# ESIOT.net
KiCad netlist of a schematic drawn in EasyEDA Pro
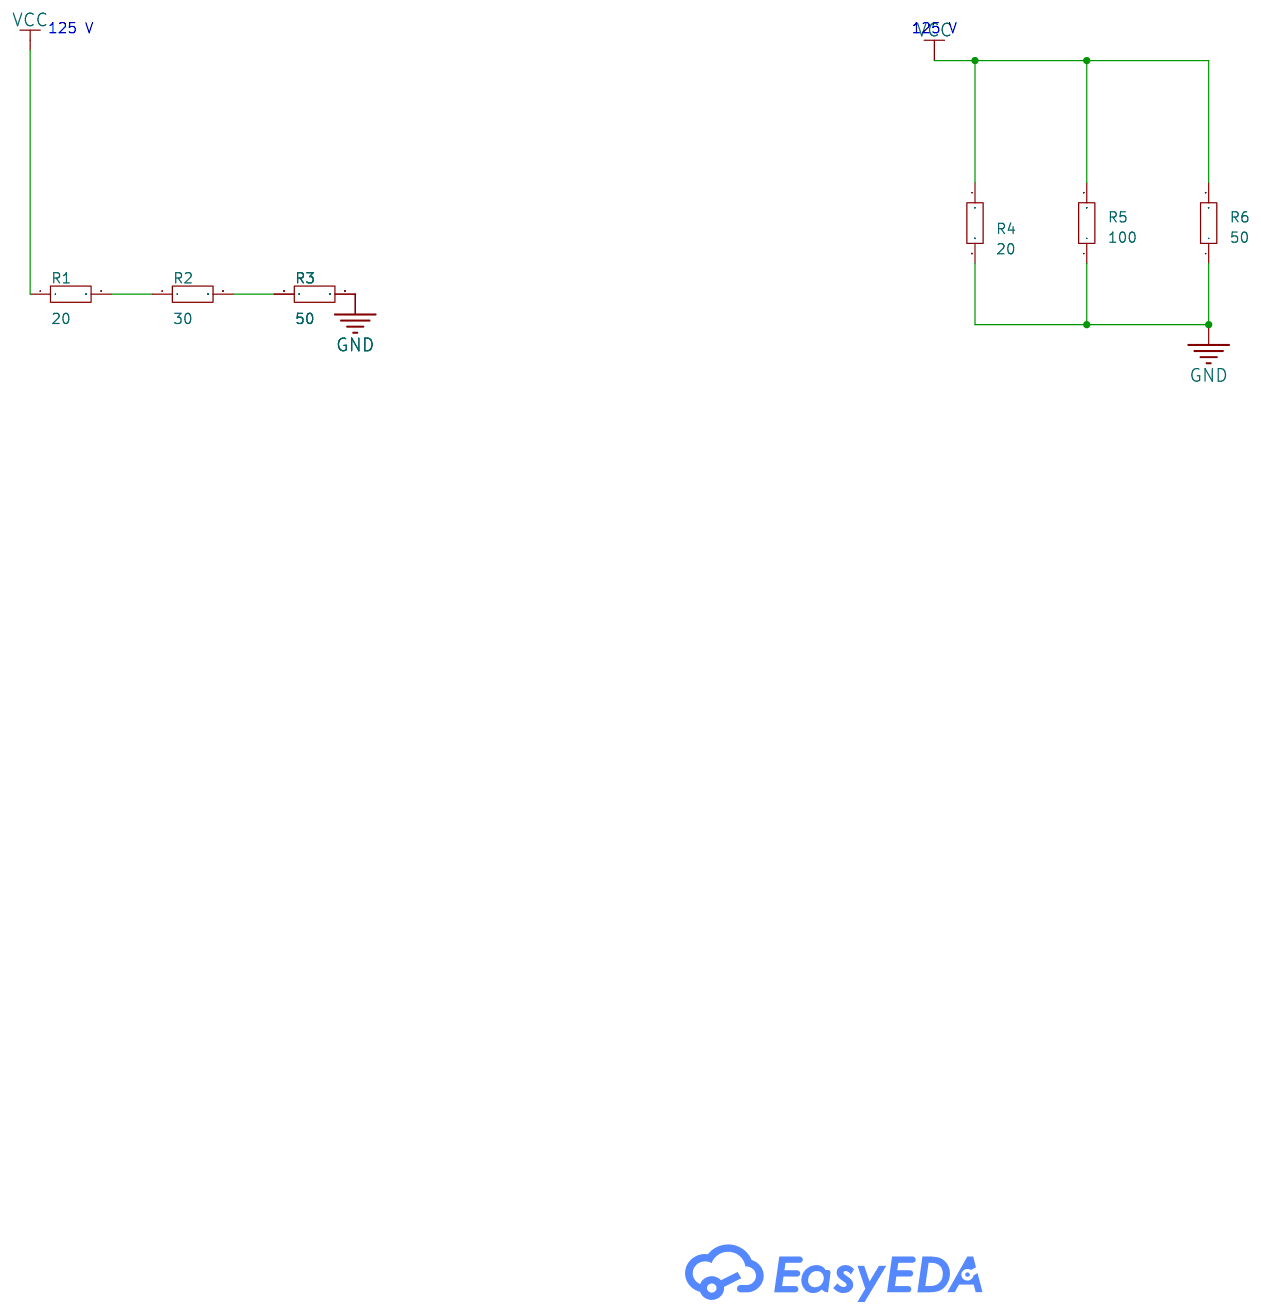
[diagram p0: P1]
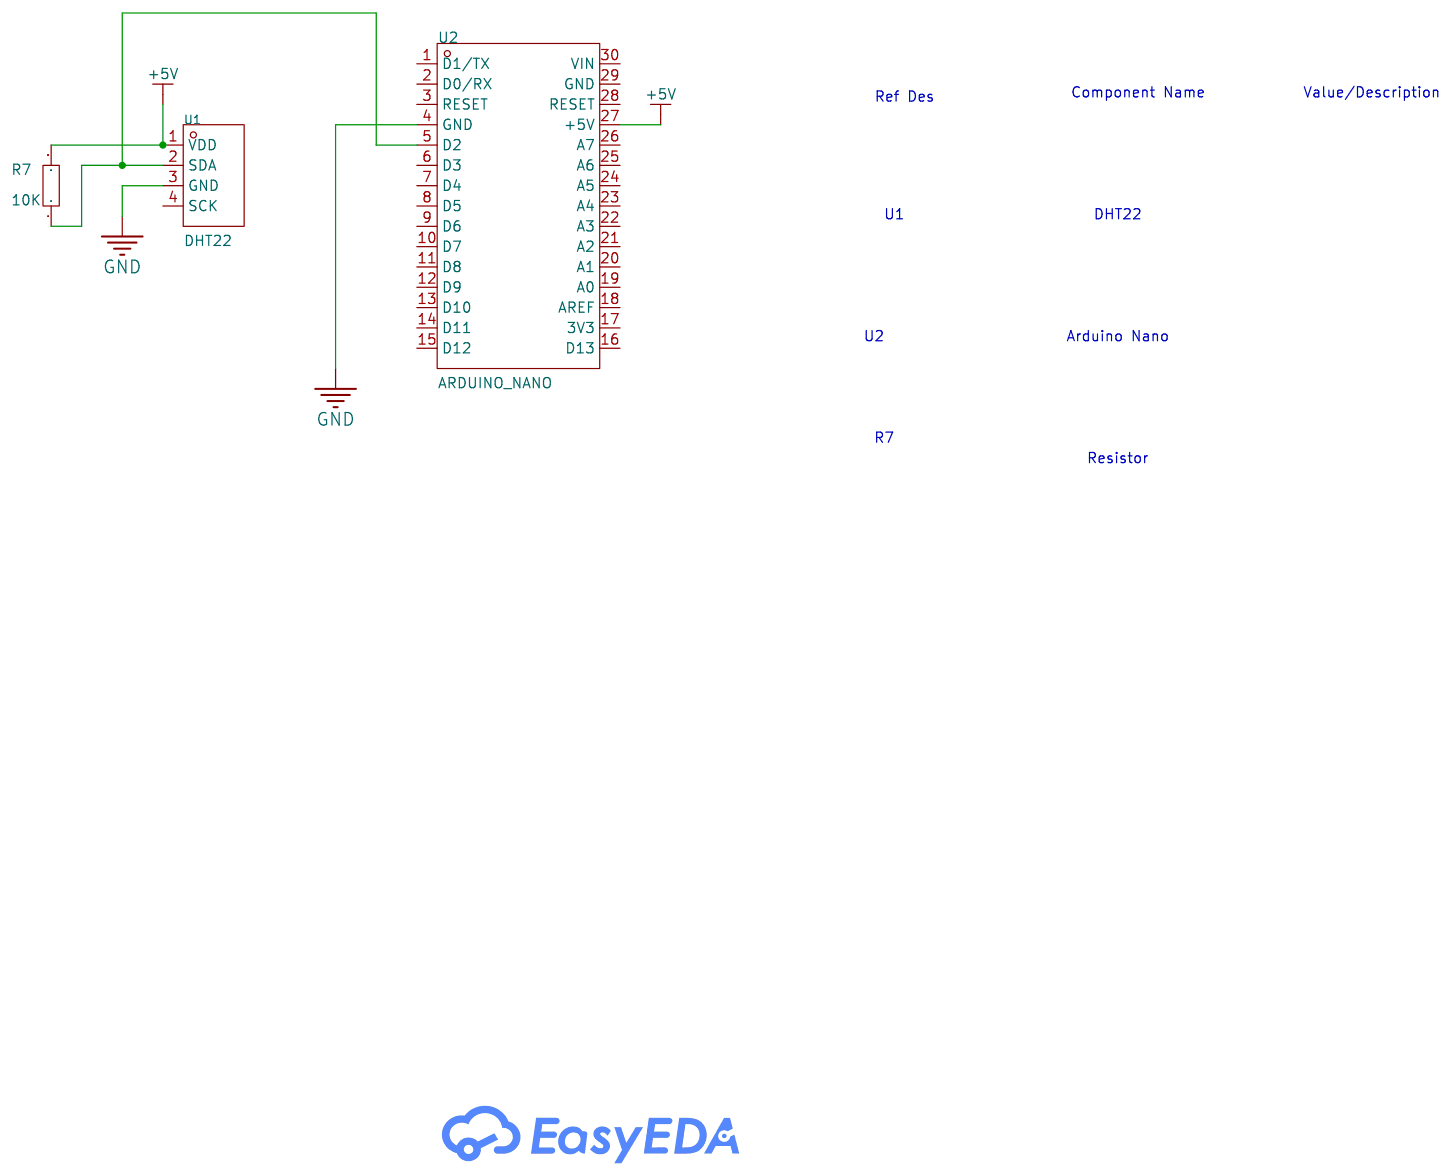
[diagram p1: P2]

(export (version "E")
  (design (tool "Eeschema 10.0.6"))
  (components
    (comp (ref "R1") (value "20") (footprint "easyedapro:R0603") (libsource (lib "easyedapro") (part "Res")))
    (comp (ref "R2") (value "30") (footprint "easyedapro:R0603") (libsource (lib "easyedapro") (part "Res")))
    (comp (ref "R3") (value "50") (footprint "easyedapro:R0603") (libsource (lib "easyedapro") (part "Res")))
    (comp (ref "R4") (value "20") (footprint "easyedapro:R0603") (libsource (lib "easyedapro") (part "Res")))
    (comp (ref "R5") (value "100") (footprint "easyedapro:R0603") (libsource (lib "easyedapro") (part "Res")))
    (comp (ref "R6") (value "50") (footprint "easyedapro:R0603") (libsource (lib "easyedapro") (part "Res")))
    (comp (ref "R7") (value "10K") (footprint "easyedapro:R0603") (libsource (lib "easyedapro") (part "Res")))
    (comp (ref "U1")
      (value "DHT22")
      (footprint "easyedapro:SENSOR-TH_HAIGU_DHT22")
      (fields (field (name "Manufacturer") "HAIGU(广州海谷)"))
      (libsource (lib "easyedapro") (part "DHT22"))
    )
    (comp (ref "U2")
      (value "ARDUINO_NANO")
      (footprint "easyedapro:COMM-TH_ARDUINO_NANO")
      (libsource (lib "easyedapro") (part "ARDUINO_NANO"))
    )
  )
  (nets
    (net (code "1") (name "+5V") (class "Default")
      (node (ref "R7") (pin "2") (pinfunction "2_2") (pintype "input"))
      (node (ref "U1") (pin "1") (pinfunction "VDD_1") (pintype "input"))
      (node (ref "U2") (pin "27") (pinfunction "+5V_27") (pintype "unspecified"))
    )
    (net (code "2") (name "GND") (class "Default")
      (node (ref "R3") (pin "2") (pinfunction "2_2") (pintype "input"))
      (node (ref "R4") (pin "2") (pinfunction "2_2") (pintype "input"))
      (node (ref "R5") (pin "1") (pinfunction "1_1") (pintype "input"))
      (node (ref "R6") (pin "1") (pinfunction "1_1") (pintype "input"))
      (node (ref "U1") (pin "3") (pinfunction "GND_3") (pintype "input"))
      (node (ref "U2") (pin "4") (pinfunction "GND_4") (pintype "unspecified"))
    )
    (net (code "3") (name "Net-(R1-Pad2)") (class "Default")
      (node (ref "R1") (pin "2") (pinfunction "2_2") (pintype "input"))
      (node (ref "R2") (pin "1") (pinfunction "1_1") (pintype "input"))
    )
    (net (code "4") (name "Net-(R2-Pad2)") (class "Default")
      (node (ref "R2") (pin "2") (pinfunction "2_2") (pintype "input"))
      (node (ref "R3") (pin "1") (pinfunction "1_1") (pintype "input"))
    )
    (net (code "5") (name "Net-(U1-SDA)") (class "Default")
      (node (ref "R7") (pin "1") (pinfunction "1_1") (pintype "input"))
      (node (ref "U1") (pin "2") (pinfunction "SDA_2") (pintype "input"))
      (node (ref "U2") (pin "5") (pinfunction "D2_5") (pintype "unspecified"))
    )
    (net (code "6") (name "VCC") (class "Default")
      (node (ref "R1") (pin "1") (pinfunction "1_1") (pintype "input"))
      (node (ref "R4") (pin "1") (pinfunction "1_1") (pintype "input"))
      (node (ref "R5") (pin "2") (pinfunction "2_2") (pintype "input"))
      (node (ref "R6") (pin "2") (pinfunction "2_2") (pintype "input"))
    )
    (net (code "7") (name "unconnected-(U1-SCK-Pad4)") (class "Default")
      (node (ref "U1") (pin "4") (pinfunction "SCK_4") (pintype "input"))
    )
    (net (code "8") (name "unconnected-(U2-3V3-Pad17)") (class "Default")
      (node (ref "U2") (pin "17") (pinfunction "3V3_17") (pintype "unspecified"))
    )
    (net (code "9") (name "unconnected-(U2-A0-Pad19)") (class "Default")
      (node (ref "U2") (pin "19") (pinfunction "A0_19") (pintype "unspecified"))
    )
    (net (code "10") (name "unconnected-(U2-A1-Pad20)") (class "Default")
      (node (ref "U2") (pin "20") (pinfunction "A1_20") (pintype "unspecified"))
    )
    (net (code "11") (name "unconnected-(U2-A2-Pad21)") (class "Default")
      (node (ref "U2") (pin "21") (pinfunction "A2_21") (pintype "unspecified"))
    )
    (net (code "12") (name "unconnected-(U2-A3-Pad22)") (class "Default")
      (node (ref "U2") (pin "22") (pinfunction "A3_22") (pintype "unspecified"))
    )
    (net (code "13") (name "unconnected-(U2-A4-Pad23)") (class "Default")
      (node (ref "U2") (pin "23") (pinfunction "A4_23") (pintype "unspecified"))
    )
    (net (code "14") (name "unconnected-(U2-A5-Pad24)") (class "Default")
      (node (ref "U2") (pin "24") (pinfunction "A5_24") (pintype "unspecified"))
    )
    (net (code "15") (name "unconnected-(U2-A6-Pad25)") (class "Default")
      (node (ref "U2") (pin "25") (pinfunction "A6_25") (pintype "unspecified"))
    )
    (net (code "16") (name "unconnected-(U2-A7-Pad26)") (class "Default")
      (node (ref "U2") (pin "26") (pinfunction "A7_26") (pintype "unspecified"))
    )
    (net (code "17") (name "unconnected-(U2-AREF-Pad18)") (class "Default")
      (node (ref "U2") (pin "18") (pinfunction "AREF_18") (pintype "unspecified"))
    )
    (net (code "18") (name "unconnected-(U2-D0{slash}RX-Pad2)") (class "Default")
      (node (ref "U2") (pin "2") (pinfunction "D0/RX_2") (pintype "unspecified"))
    )
    (net (code "19") (name "unconnected-(U2-D1{slash}TX-Pad1)") (class "Default")
      (node (ref "U2") (pin "1") (pinfunction "D1/TX_1") (pintype "unspecified"))
    )
    (net (code "20") (name "unconnected-(U2-D3-Pad6)") (class "Default")
      (node (ref "U2") (pin "6") (pinfunction "D3_6") (pintype "unspecified"))
    )
    (net (code "21") (name "unconnected-(U2-D4-Pad7)") (class "Default")
      (node (ref "U2") (pin "7") (pinfunction "D4_7") (pintype "unspecified"))
    )
    (net (code "22") (name "unconnected-(U2-D5-Pad8)") (class "Default")
      (node (ref "U2") (pin "8") (pinfunction "D5_8") (pintype "unspecified"))
    )
    (net (code "23") (name "unconnected-(U2-D6-Pad9)") (class "Default")
      (node (ref "U2") (pin "9") (pinfunction "D6_9") (pintype "unspecified"))
    )
    (net (code "24") (name "unconnected-(U2-D7-Pad10)") (class "Default")
      (node (ref "U2") (pin "10") (pinfunction "D7_10") (pintype "unspecified"))
    )
    (net (code "25") (name "unconnected-(U2-D8-Pad11)") (class "Default")
      (node (ref "U2") (pin "11") (pinfunction "D8_11") (pintype "unspecified"))
    )
    (net (code "26") (name "unconnected-(U2-D9-Pad12)") (class "Default")
      (node (ref "U2") (pin "12") (pinfunction "D9_12") (pintype "unspecified"))
    )
    (net (code "27") (name "unconnected-(U2-D10-Pad13)") (class "Default")
      (node (ref "U2") (pin "13") (pinfunction "D10_13") (pintype "unspecified"))
    )
    (net (code "28") (name "unconnected-(U2-D11-Pad14)") (class "Default")
      (node (ref "U2") (pin "14") (pinfunction "D11_14") (pintype "unspecified"))
    )
    (net (code "29") (name "unconnected-(U2-D12-Pad15)") (class "Default")
      (node (ref "U2") (pin "15") (pinfunction "D12_15") (pintype "unspecified"))
    )
    (net (code "30") (name "unconnected-(U2-D13-Pad16)") (class "Default")
      (node (ref "U2") (pin "16") (pinfunction "D13_16") (pintype "unspecified"))
    )
    (net (code "31") (name "unconnected-(U2-GND-Pad29)") (class "Default")
      (node (ref "U2") (pin "29") (pinfunction "GND_29") (pintype "unspecified"))
    )
    (net (code "32") (name "unconnected-(U2-RESET-Pad3)") (class "Default")
      (node (ref "U2") (pin "3") (pinfunction "RESET_3") (pintype "unspecified"))
    )
    (net (code "33") (name "unconnected-(U2-RESET-Pad28)") (class "Default")
      (node (ref "U2") (pin "28") (pinfunction "RESET_28") (pintype "unspecified"))
    )
    (net (code "34") (name "unconnected-(U2-VIN-Pad30)") (class "Default")
      (node (ref "U2") (pin "30") (pinfunction "VIN_30") (pintype "unspecified"))
    )
  )
)
